# CAN_USB_M_V1.net
KiCad netlist of a schematic drawn in Altium Designer
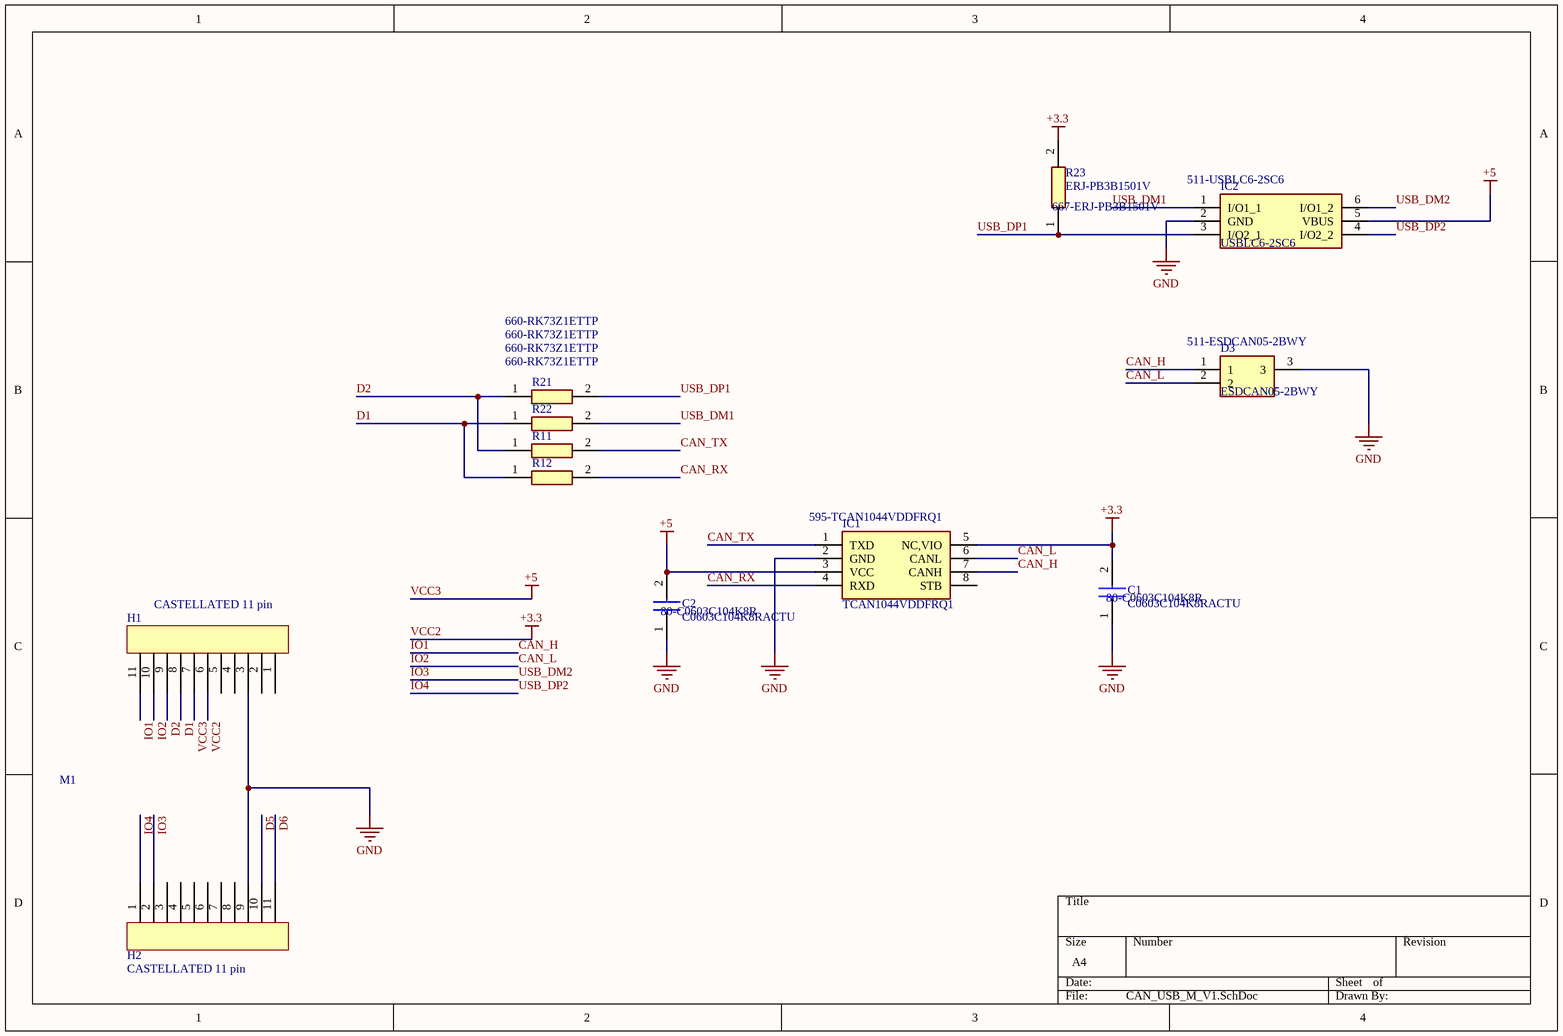
[diagram p0: CAN_USB_M_V1.SchDoc]

(export (version "E")
  (design (tool "Eeschema 10.0.6"))
  (components
    (comp (ref "C1")
      (value "C0603C104K8RACTU")
      (footprint "SamacSys:CAPC1608X90N")
      (description "Capacitor")
      (fields (field (name "SUPPLIER PART NUMBER 1") "80-C0603C104K8R"))
      (libsource (lib "SamacSys") (part "C0603C104K8RACTU"))
    )
    (comp (ref "C2")
      (value "C0603C104K8RACTU")
      (footprint "SamacSys:CAPC1608X90N")
      (description "Capacitor")
      (fields (field (name "SUPPLIER PART NUMBER 1") "80-C0603C104K8R"))
      (libsource (lib "SamacSys") (part "C0603C104K8RACTU"))
    )
    (comp (ref "D3")
      (value "ESDCAN05-2BWY")
      (footprint "SamacSys:SOT65P210X110-3N")
      (description "TVS Diode (Bi-directional)")
      (fields
        (field (name "MOUSER2 PART NUMBER") "511-ESDCAN05-2BWY")
        (field (name "SUPPLIER PART NUMBER 1") "511-ESDCAN05-2BWY")
      )
      (libsource (lib "SamacSys") (part "ESDCAN05-2BWY"))
    )
    (comp (ref "H1")
      (value "CASTELLATED 11 pin")
      (footprint "CASTELLATED 11 pin")
      (libsource (lib "USIB") (part "CASTELLATED 11 pin"))
    )
    (comp (ref "H2")
      (value "CASTELLATED 11 pin")
      (footprint "CASTELLATED 11 pin")
      (libsource (lib "") (part "CASTELLATED 11 pin_1"))
    )
    (comp (ref "IC1")
      (value "TCAN1044VDDFRQ1")
      (footprint "SamacSys:SOT65P280X110-8N")
      (description "Integrated Circuit")
      (fields (field (name "SUPPLIER PART NUMBER 1") "595-TCAN1044VDDFRQ1"))
      (libsource (lib "SamacSys") (part "TCAN1044VDDFRQ1"))
    )
    (comp (ref "IC2")
      (value "USBLC6-2SC6")
      (footprint "SamacSys:SOT95P280X145-6N")
      (description "Integrated Circuit")
      (fields
        (field (name "MOUSER2 PART NUMBER") "511-USBLC6-2SC6")
        (field (name "SUPPLIER PART NUMBER 1") "511-USBLC6-2SC6")
      )
      (libsource (lib "SamacSys") (part "USBLC6-2SC6"))
    )
    (comp (ref "R11")
      (value "RK73Z1ETTP")
      (footprint "SamacSys:RESC1005X40N")
      (description "Resistor")
      (fields (field (name "SUPPLIER PART NUMBER 1") "660-RK73Z1ETTP"))
      (libsource (lib "*") (part "RK73Z1ETTP"))
    )
    (comp (ref "R12")
      (value "RK73Z1ETTP")
      (footprint "SamacSys:RESC1005X40N")
      (description "Resistor")
      (fields (field (name "SUPPLIER PART NUMBER 1") "660-RK73Z1ETTP"))
      (libsource (lib "*") (part "RK73Z1ETTP"))
    )
    (comp (ref "R21")
      (value "RK73Z1ETTP")
      (footprint "SamacSys:RESC1005X40N")
      (description "Resistor")
      (fields (field (name "SUPPLIER PART NUMBER 1") "660-RK73Z1ETTP"))
      (libsource (lib "*") (part "RK73Z1ETTP"))
    )
    (comp (ref "R22")
      (value "RK73Z1ETTP")
      (footprint "SamacSys:RESC1005X40N")
      (description "Resistor")
      (fields (field (name "SUPPLIER PART NUMBER 1") "660-RK73Z1ETTP"))
      (libsource (lib "*") (part "RK73Z1ETTP"))
    )
    (comp (ref "R23")
      (value "ERJ-PB3B1501V")
      (footprint "SamacSys:RESC1608X55N")
      (description "Resistor")
      (fields (field (name "SUPPLIER PART NUMBER 1") "667-ERJ-PB3B1501V"))
      (libsource (lib "SamacSys") (part "ERJ-PB3B1501V"))
    )
  )
  (nets
    (net (code "1") (name "+3.3") (class "Default")
      (node (ref "C1") (pin "2") (pinfunction "2_2") (pintype "passive"))
      (node (ref "H1") (pin "6") (pintype "passive"))
      (node (ref "IC1") (pin "5") (pinfunction "NC,VIO_5") (pintype "passive"))
      (node (ref "R23") (pin "2") (pinfunction "2_2") (pintype "passive"))
    )
    (net (code "2") (name "+5") (class "Default")
      (node (ref "C2") (pin "2") (pinfunction "2_2") (pintype "passive"))
      (node (ref "H1") (pin "7") (pintype "passive"))
      (node (ref "IC1") (pin "3") (pinfunction "VCC_3") (pintype "passive"))
      (node (ref "IC2") (pin "5") (pinfunction "VBUS_5") (pintype "passive"))
    )
    (net (code "3") (name "/CAN_H") (class "Default")
      (node (ref "D3") (pin "1") (pinfunction "1_1") (pintype "passive"))
      (node (ref "H1") (pin "11") (pintype "passive"))
      (node (ref "IC1") (pin "7") (pinfunction "CANH_7") (pintype "passive"))
    )
    (net (code "4") (name "/CAN_L") (class "Default")
      (node (ref "D3") (pin "2") (pinfunction "2_2") (pintype "passive"))
      (node (ref "H1") (pin "10") (pintype "passive"))
      (node (ref "IC1") (pin "6") (pinfunction "CANL_6") (pintype "passive"))
    )
    (net (code "5") (name "/CAN_RX") (class "Default")
      (node (ref "IC1") (pin "4") (pinfunction "RXD_4") (pintype "passive"))
      (node (ref "R12") (pin "2") (pinfunction "2_2") (pintype "passive"))
    )
    (net (code "6") (name "/CAN_TX") (class "Default")
      (node (ref "IC1") (pin "1") (pinfunction "TXD_1") (pintype "passive"))
      (node (ref "R11") (pin "2") (pinfunction "2_2") (pintype "passive"))
    )
    (net (code "7") (name "/D1") (class "Default")
      (node (ref "H1") (pin "8") (pintype "passive"))
      (node (ref "R12") (pin "1") (pinfunction "1_1") (pintype "passive"))
      (node (ref "R22") (pin "1") (pinfunction "1_1") (pintype "passive"))
    )
    (net (code "8") (name "/D2") (class "Default")
      (node (ref "H1") (pin "9") (pintype "passive"))
      (node (ref "R11") (pin "1") (pinfunction "1_1") (pintype "passive"))
      (node (ref "R21") (pin "1") (pinfunction "1_1") (pintype "passive"))
    )
    (net (code "9") (name "/D5") (class "Default") (node (ref "H2") (pin "10") (pintype "passive")))
    (net (code "10") (name "/D6") (class "Default") (node (ref "H2") (pin "11") (pintype "passive")))
    (net (code "11") (name "/IO3") (class "Default")
      (node (ref "H2") (pin "2") (pintype "passive"))
      (node (ref "IC2") (pin "6") (pinfunction "I/O1_2_6") (pintype "passive"))
    )
    (net (code "12") (name "/IO4") (class "Default")
      (node (ref "H2") (pin "1") (pintype "passive"))
      (node (ref "IC2") (pin "4") (pinfunction "I/O2_2_4") (pintype "passive"))
    )
    (net (code "13") (name "/USB_DM1") (class "Default")
      (node (ref "IC2") (pin "1") (pinfunction "I/O1_1_1") (pintype "passive"))
      (node (ref "R22") (pin "2") (pinfunction "2_2") (pintype "passive"))
    )
    (net (code "14") (name "/USB_DP1") (class "Default")
      (node (ref "IC2") (pin "3") (pinfunction "I/O2_1_3") (pintype "passive"))
      (node (ref "R21") (pin "2") (pinfunction "2_2") (pintype "passive"))
      (node (ref "R23") (pin "1") (pinfunction "1_1") (pintype "passive"))
    )
    (net (code "15") (name "GND") (class "Default")
      (node (ref "C1") (pin "1") (pinfunction "1_1") (pintype "passive"))
      (node (ref "C2") (pin "1") (pinfunction "1_1") (pintype "passive"))
      (node (ref "D3") (pin "3") (pinfunction "3_3") (pintype "passive"))
      (node (ref "H1") (pin "3") (pintype "passive"))
      (node (ref "H2") (pin "9") (pintype "passive"))
      (node (ref "IC1") (pin "2") (pinfunction "GND_2") (pintype "passive"))
      (node (ref "IC2") (pin "2") (pinfunction "GND_2") (pintype "passive"))
    )
    (net (code "16") (name "unconnected-(H1-Pad1)") (class "Default")
      (node (ref "H1") (pin "1") (pintype "passive"))
    )
    (net (code "17") (name "unconnected-(H1-Pad2)") (class "Default")
      (node (ref "H1") (pin "2") (pintype "passive"))
    )
    (net (code "18") (name "unconnected-(H1-Pad4)") (class "Default")
      (node (ref "H1") (pin "4") (pintype "passive"))
    )
    (net (code "19") (name "unconnected-(H1-Pad5)") (class "Default")
      (node (ref "H1") (pin "5") (pintype "passive"))
    )
    (net (code "20") (name "unconnected-(H2-Pad3)") (class "Default")
      (node (ref "H2") (pin "3") (pintype "passive"))
    )
    (net (code "21") (name "unconnected-(H2-Pad4)") (class "Default")
      (node (ref "H2") (pin "4") (pintype "passive"))
    )
    (net (code "22") (name "unconnected-(H2-Pad5)") (class "Default")
      (node (ref "H2") (pin "5") (pintype "passive"))
    )
    (net (code "23") (name "unconnected-(H2-Pad6)") (class "Default")
      (node (ref "H2") (pin "6") (pintype "passive"))
    )
    (net (code "24") (name "unconnected-(H2-Pad7)") (class "Default")
      (node (ref "H2") (pin "7") (pintype "passive"))
    )
    (net (code "25") (name "unconnected-(H2-Pad8)") (class "Default")
      (node (ref "H2") (pin "8") (pintype "passive"))
    )
    (net (code "26") (name "unconnected-(IC1-STB-Pad8)") (class "Default")
      (node (ref "IC1") (pin "8") (pinfunction "STB_8") (pintype "passive"))
    )
  )
)
